# Antena_lora_receptora.net
KiCad netlist of a schematic drawn in Altium Designer
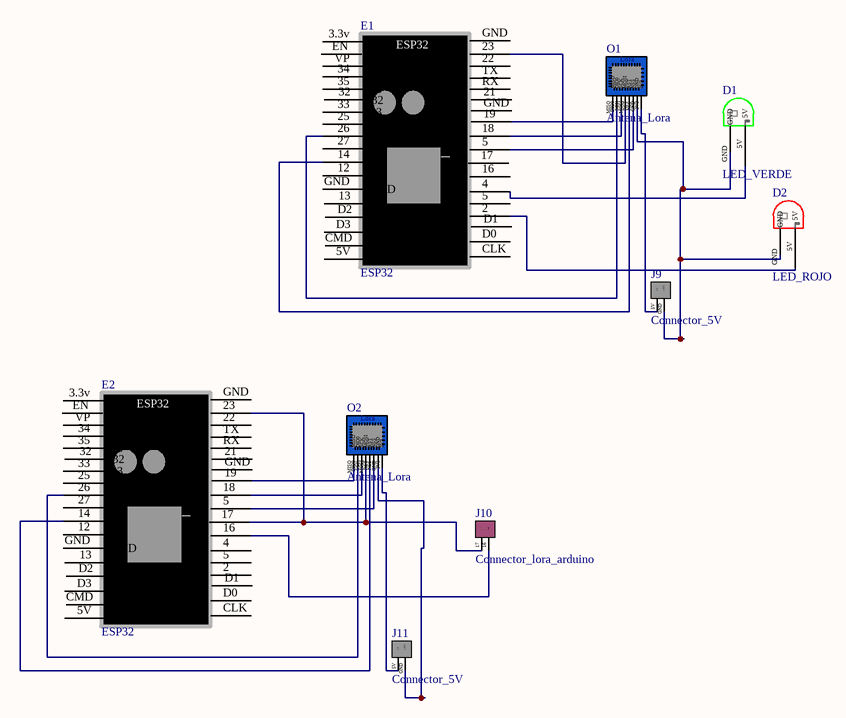
[diagram p0: Antena_lora_receptora.SchDoc]

(export (version "E")
  (design (tool "Eeschema 10.0.6"))
  (components
    (comp (ref "D1") (value "LED_VERDE") (libsource (lib "RBR-RAMON") (part "LED_VERDE")))
    (comp (ref "D2") (value "LED_ROJO") (libsource (lib "RBR-RAMON") (part "LED_ROJO")))
    (comp (ref "E1") (value "ESP32") (libsource (lib "RBR-RAMON") (part "ESP32")))
    (comp (ref "E2") (value "ESP32") (libsource (lib "RBR-RAMON") (part "ESP32")))
    (comp (ref "J9")
      (value "Connector_5V")
      (footprint "Conector_5V")
      (libsource (lib "RBR-RAMON") (part "Connector_5V"))
    )
    (comp (ref "J10")
      (value "Connector_lora_arduino")
      (footprint "Conector_lora_arduino")
      (libsource (lib "RBR-RAMON") (part "Connector_lora_arduino"))
    )
    (comp (ref "J11")
      (value "Connector_5V")
      (footprint "Conector_5V")
      (libsource (lib "RBR-RAMON") (part "Connector_5V"))
    )
    (comp (ref "O1") (value "Antena_Lora") (libsource (lib "RBR-RAMON") (part "Antena_Lora")))
    (comp (ref "O2") (value "Antena_Lora") (libsource (lib "RBR-RAMON") (part "Antena_Lora")))
  )
  (nets
    (net (code "1") (name "Net-(D1-Pad5V)") (class "Default")
      (node (ref "D1") (pin "5V") (pinfunction "5V_5V") (pintype "passive"))
      (node (ref "E1") (pin "4") (pinfunction "4_4") (pintype "passive"))
    )
    (net (code "2") (name "Net-(D1-PadGND)") (class "Default")
      (node (ref "D1") (pin "GND") (pinfunction "GND_GND") (pintype "passive"))
      (node (ref "D2") (pin "GND") (pinfunction "GND_GND") (pintype "passive"))
      (node (ref "J9") (pin "GND") (pinfunction "GND_GND") (pintype "passive"))
      (node (ref "O1") (pin "GND") (pinfunction "GND_GND") (pintype "passive"))
    )
    (net (code "3") (name "Net-(D2-Pad5V)") (class "Default")
      (node (ref "D2") (pin "5V") (pinfunction "5V_5V") (pintype "passive"))
      (node (ref "E1") (pin "2") (pinfunction "2_2") (pintype "passive"))
    )
    (net (code "4") (name "Net-(E1-Pad5)_1") (class "Default")
      (node (ref "E1") (pin "5") (pinfunction "5_5") (pintype "passive"))
      (node (ref "O1") (pin "NSS") (pinfunction "NSS_NSS") (pintype "passive"))
    )
    (net (code "5") (name "Net-(E1-Pad14)") (class "Default")
      (node (ref "E1") (pin "14") (pinfunction "14_14") (pintype "passive"))
      (node (ref "O1") (pin "RST") (pinfunction "RST_RST") (pintype "passive"))
    )
    (net (code "6") (name "Net-(E1-Pad18)") (class "Default")
      (node (ref "E1") (pin "18") (pinfunction "18_18") (pintype "passive"))
      (node (ref "O1") (pin "SCK") (pinfunction "SCK_SCK") (pintype "passive"))
    )
    (net (code "7") (name "Net-(E1-Pad19)") (class "Default")
      (node (ref "E1") (pin "19") (pinfunction "19_19") (pintype "passive"))
      (node (ref "O1") (pin "MISO") (pinfunction "MISO_MISO") (pintype "passive"))
    )
    (net (code "8") (name "Net-(E1-Pad23)") (class "Default")
      (node (ref "E1") (pin "23") (pinfunction "23_23") (pintype "passive"))
      (node (ref "O1") (pin "MOSI") (pinfunction "MOSI_MOSI") (pintype "passive"))
    )
    (net (code "9") (name "Net-(E1-Pad26)") (class "Default")
      (node (ref "E1") (pin "26") (pinfunction "26_26") (pintype "passive"))
      (node (ref "O1") (pin "DIO0") (pinfunction "DIO0_DIO0") (pintype "passive"))
    )
    (net (code "10") (name "Net-(E2-Pad5)_1") (class "Default")
      (node (ref "E2") (pin "5") (pinfunction "5_5") (pintype "passive"))
      (node (ref "O2") (pin "NSS") (pinfunction "NSS_NSS") (pintype "passive"))
    )
    (net (code "11") (name "Net-(E2-Pad14)") (class "Default")
      (node (ref "E2") (pin "14") (pinfunction "14_14") (pintype "passive"))
      (node (ref "O2") (pin "RST") (pinfunction "RST_RST") (pintype "passive"))
    )
    (net (code "12") (name "Net-(E2-Pad16)") (class "Default")
      (node (ref "E2") (pin "16") (pinfunction "16_16") (pintype "passive"))
      (node (ref "J10") (pin "16") (pinfunction "16_16") (pintype "passive"))
    )
    (net (code "13") (name "Net-(E2-Pad17)") (class "Default")
      (node (ref "E2") (pin "17") (pinfunction "17_17") (pintype "passive"))
      (node (ref "E2") (pin "23") (pinfunction "23_23") (pintype "passive"))
      (node (ref "J10") (pin "17") (pinfunction "17_17") (pintype "passive"))
      (node (ref "O2") (pin "MOSI") (pinfunction "MOSI_MOSI") (pintype "passive"))
    )
    (net (code "14") (name "Net-(E2-Pad18)") (class "Default")
      (node (ref "E2") (pin "18") (pinfunction "18_18") (pintype "passive"))
      (node (ref "O2") (pin "SCK") (pinfunction "SCK_SCK") (pintype "passive"))
    )
    (net (code "15") (name "Net-(E2-Pad19)") (class "Default")
      (node (ref "E2") (pin "19") (pinfunction "19_19") (pintype "passive"))
      (node (ref "O2") (pin "MISO") (pinfunction "MISO_MISO") (pintype "passive"))
    )
    (net (code "16") (name "Net-(E2-Pad26)") (class "Default")
      (node (ref "E2") (pin "26") (pinfunction "26_26") (pintype "passive"))
      (node (ref "O2") (pin "DIO0") (pinfunction "DIO0_DIO0") (pintype "passive"))
    )
    (net (code "17") (name "Net-(J9-Pad5V)") (class "Default")
      (node (ref "J9") (pin "5V") (pinfunction "5V_5V") (pintype "passive"))
      (node (ref "O1") (pin "3V3") (pinfunction "3V3_3V3") (pintype "passive"))
    )
    (net (code "18") (name "Net-(J11-Pad5V)") (class "Default")
      (node (ref "J11") (pin "5V") (pinfunction "5V_5V") (pintype "passive"))
      (node (ref "O2") (pin "3V3") (pinfunction "3V3_3V3") (pintype "passive"))
    )
    (net (code "19") (name "Net-(J11-PadGND)") (class "Default")
      (node (ref "J11") (pin "GND") (pinfunction "GND_GND") (pintype "passive"))
      (node (ref "O2") (pin "GND") (pinfunction "GND_GND") (pintype "passive"))
    )
    (net (code "20") (name "unconnected-(E1-Pad3.3v)") (class "Default")
      (node (ref "E1") (pin "3.3v") (pinfunction "3.3v_3.3v") (pintype "passive"))
    )
    (net (code "21") (name "unconnected-(E1-Pad5)") (class "Default")
      (node (ref "E1") (pin "5") (pinfunction "5_5") (pintype "passive"))
    )
    (net (code "22") (name "unconnected-(E1-Pad5V)") (class "Default")
      (node (ref "E1") (pin "5V") (pinfunction "5V_5V") (pintype "passive"))
    )
    (net (code "23") (name "unconnected-(E1-Pad12)") (class "Default")
      (node (ref "E1") (pin "12") (pinfunction "12_12") (pintype "passive"))
    )
    (net (code "24") (name "unconnected-(E1-Pad13)") (class "Default")
      (node (ref "E1") (pin "13") (pinfunction "13_13") (pintype "passive"))
    )
    (net (code "25") (name "unconnected-(E1-Pad16)") (class "Default")
      (node (ref "E1") (pin "16") (pinfunction "16_16") (pintype "passive"))
    )
    (net (code "26") (name "unconnected-(E1-Pad17)") (class "Default")
      (node (ref "E1") (pin "17") (pinfunction "17_17") (pintype "passive"))
    )
    (net (code "27") (name "unconnected-(E1-Pad21)") (class "Default")
      (node (ref "E1") (pin "21") (pinfunction "21_21") (pintype "passive"))
    )
    (net (code "28") (name "unconnected-(E1-Pad22)") (class "Default")
      (node (ref "E1") (pin "22") (pinfunction "22_22") (pintype "passive"))
    )
    (net (code "29") (name "unconnected-(E1-Pad25)") (class "Default")
      (node (ref "E1") (pin "25") (pinfunction "25_25") (pintype "passive"))
    )
    (net (code "30") (name "unconnected-(E1-Pad27)") (class "Default")
      (node (ref "E1") (pin "27") (pinfunction "27_27") (pintype "passive"))
    )
    (net (code "31") (name "unconnected-(E1-Pad32)") (class "Default")
      (node (ref "E1") (pin "32") (pinfunction "32_32") (pintype "passive"))
    )
    (net (code "32") (name "unconnected-(E1-Pad33)") (class "Default")
      (node (ref "E1") (pin "33") (pinfunction "33_33") (pintype "passive"))
    )
    (net (code "33") (name "unconnected-(E1-Pad34)") (class "Default")
      (node (ref "E1") (pin "34") (pinfunction "34_34") (pintype "passive"))
    )
    (net (code "34") (name "unconnected-(E1-Pad35)") (class "Default")
      (node (ref "E1") (pin "35") (pinfunction "35_35") (pintype "passive"))
    )
    (net (code "35") (name "unconnected-(E1-PadCLK)") (class "Default")
      (node (ref "E1") (pin "CLK") (pinfunction "CLK_CLK") (pintype "passive"))
    )
    (net (code "36") (name "unconnected-(E1-PadCMD)") (class "Default")
      (node (ref "E1") (pin "CMD") (pinfunction "CMD_CMD") (pintype "passive"))
    )
    (net (code "37") (name "unconnected-(E1-PadD0)") (class "Default")
      (node (ref "E1") (pin "D0") (pinfunction "D0_D0") (pintype "passive"))
    )
    (net (code "38") (name "unconnected-(E1-PadD1)") (class "Default")
      (node (ref "E1") (pin "D1") (pinfunction "D1_D1") (pintype "passive"))
    )
    (net (code "39") (name "unconnected-(E1-PadD2)") (class "Default")
      (node (ref "E1") (pin "D2") (pinfunction "D2_D2") (pintype "passive"))
    )
    (net (code "40") (name "unconnected-(E1-PadD3)") (class "Default")
      (node (ref "E1") (pin "D3") (pinfunction "D3_D3") (pintype "passive"))
    )
    (net (code "41") (name "unconnected-(E1-PadEN)") (class "Default")
      (node (ref "E1") (pin "EN") (pinfunction "EN_EN") (pintype "passive"))
    )
    (net (code "42") (name "unconnected-(E1-PadGND)") (class "Default")
      (node (ref "E1") (pin "GND") (pinfunction "GND_GND") (pintype "passive"))
    )
    (net (code "43") (name "unconnected-(E1-PadGND)_1") (class "Default")
      (node (ref "E1") (pin "GND") (pinfunction "GND_GND") (pintype "passive"))
    )
    (net (code "44") (name "unconnected-(E1-PadGND)_2") (class "Default")
      (node (ref "E1") (pin "GND") (pinfunction "GND_GND") (pintype "passive"))
    )
    (net (code "45") (name "unconnected-(E1-PadRX)") (class "Default")
      (node (ref "E1") (pin "RX") (pinfunction "RX_RX") (pintype "passive"))
    )
    (net (code "46") (name "unconnected-(E1-PadTX)") (class "Default")
      (node (ref "E1") (pin "TX") (pinfunction "TX_TX") (pintype "passive"))
    )
    (net (code "47") (name "unconnected-(E1-PadVP)") (class "Default")
      (node (ref "E1") (pin "VP") (pinfunction "VP_VP") (pintype "passive"))
    )
    (net (code "48") (name "unconnected-(E2-Pad2)") (class "Default")
      (node (ref "E2") (pin "2") (pinfunction "2_2") (pintype "passive"))
    )
    (net (code "49") (name "unconnected-(E2-Pad3.3v)") (class "Default")
      (node (ref "E2") (pin "3.3v") (pinfunction "3.3v_3.3v") (pintype "passive"))
    )
    (net (code "50") (name "unconnected-(E2-Pad4)") (class "Default")
      (node (ref "E2") (pin "4") (pinfunction "4_4") (pintype "passive"))
    )
    (net (code "51") (name "unconnected-(E2-Pad5)") (class "Default")
      (node (ref "E2") (pin "5") (pinfunction "5_5") (pintype "passive"))
    )
    (net (code "52") (name "unconnected-(E2-Pad5V)") (class "Default")
      (node (ref "E2") (pin "5V") (pinfunction "5V_5V") (pintype "passive"))
    )
    (net (code "53") (name "unconnected-(E2-Pad12)") (class "Default")
      (node (ref "E2") (pin "12") (pinfunction "12_12") (pintype "passive"))
    )
    (net (code "54") (name "unconnected-(E2-Pad13)") (class "Default")
      (node (ref "E2") (pin "13") (pinfunction "13_13") (pintype "passive"))
    )
    (net (code "55") (name "unconnected-(E2-Pad21)") (class "Default")
      (node (ref "E2") (pin "21") (pinfunction "21_21") (pintype "passive"))
    )
    (net (code "56") (name "unconnected-(E2-Pad22)") (class "Default")
      (node (ref "E2") (pin "22") (pinfunction "22_22") (pintype "passive"))
    )
    (net (code "57") (name "unconnected-(E2-Pad25)") (class "Default")
      (node (ref "E2") (pin "25") (pinfunction "25_25") (pintype "passive"))
    )
    (net (code "58") (name "unconnected-(E2-Pad27)") (class "Default")
      (node (ref "E2") (pin "27") (pinfunction "27_27") (pintype "passive"))
    )
    (net (code "59") (name "unconnected-(E2-Pad32)") (class "Default")
      (node (ref "E2") (pin "32") (pinfunction "32_32") (pintype "passive"))
    )
    (net (code "60") (name "unconnected-(E2-Pad33)") (class "Default")
      (node (ref "E2") (pin "33") (pinfunction "33_33") (pintype "passive"))
    )
    (net (code "61") (name "unconnected-(E2-Pad34)") (class "Default")
      (node (ref "E2") (pin "34") (pinfunction "34_34") (pintype "passive"))
    )
    (net (code "62") (name "unconnected-(E2-Pad35)") (class "Default")
      (node (ref "E2") (pin "35") (pinfunction "35_35") (pintype "passive"))
    )
    (net (code "63") (name "unconnected-(E2-PadCLK)") (class "Default")
      (node (ref "E2") (pin "CLK") (pinfunction "CLK_CLK") (pintype "passive"))
    )
    (net (code "64") (name "unconnected-(E2-PadCMD)") (class "Default")
      (node (ref "E2") (pin "CMD") (pinfunction "CMD_CMD") (pintype "passive"))
    )
    (net (code "65") (name "unconnected-(E2-PadD0)") (class "Default")
      (node (ref "E2") (pin "D0") (pinfunction "D0_D0") (pintype "passive"))
    )
    (net (code "66") (name "unconnected-(E2-PadD1)") (class "Default")
      (node (ref "E2") (pin "D1") (pinfunction "D1_D1") (pintype "passive"))
    )
    (net (code "67") (name "unconnected-(E2-PadD2)") (class "Default")
      (node (ref "E2") (pin "D2") (pinfunction "D2_D2") (pintype "passive"))
    )
    (net (code "68") (name "unconnected-(E2-PadD3)") (class "Default")
      (node (ref "E2") (pin "D3") (pinfunction "D3_D3") (pintype "passive"))
    )
    (net (code "69") (name "unconnected-(E2-PadEN)") (class "Default")
      (node (ref "E2") (pin "EN") (pinfunction "EN_EN") (pintype "passive"))
    )
    (net (code "70") (name "unconnected-(E2-PadGND)") (class "Default")
      (node (ref "E2") (pin "GND") (pinfunction "GND_GND") (pintype "passive"))
    )
    (net (code "71") (name "unconnected-(E2-PadGND)_1") (class "Default")
      (node (ref "E2") (pin "GND") (pinfunction "GND_GND") (pintype "passive"))
    )
    (net (code "72") (name "unconnected-(E2-PadGND)_2") (class "Default")
      (node (ref "E2") (pin "GND") (pinfunction "GND_GND") (pintype "passive"))
    )
    (net (code "73") (name "unconnected-(E2-PadRX)") (class "Default")
      (node (ref "E2") (pin "RX") (pinfunction "RX_RX") (pintype "passive"))
    )
    (net (code "74") (name "unconnected-(E2-PadTX)") (class "Default")
      (node (ref "E2") (pin "TX") (pinfunction "TX_TX") (pintype "passive"))
    )
    (net (code "75") (name "unconnected-(E2-PadVP)") (class "Default")
      (node (ref "E2") (pin "VP") (pinfunction "VP_VP") (pintype "passive"))
    )
  )
)
